# NNLightSwitcher_Zynq.net
KiCad netlist of a schematic drawn in Altium Designer
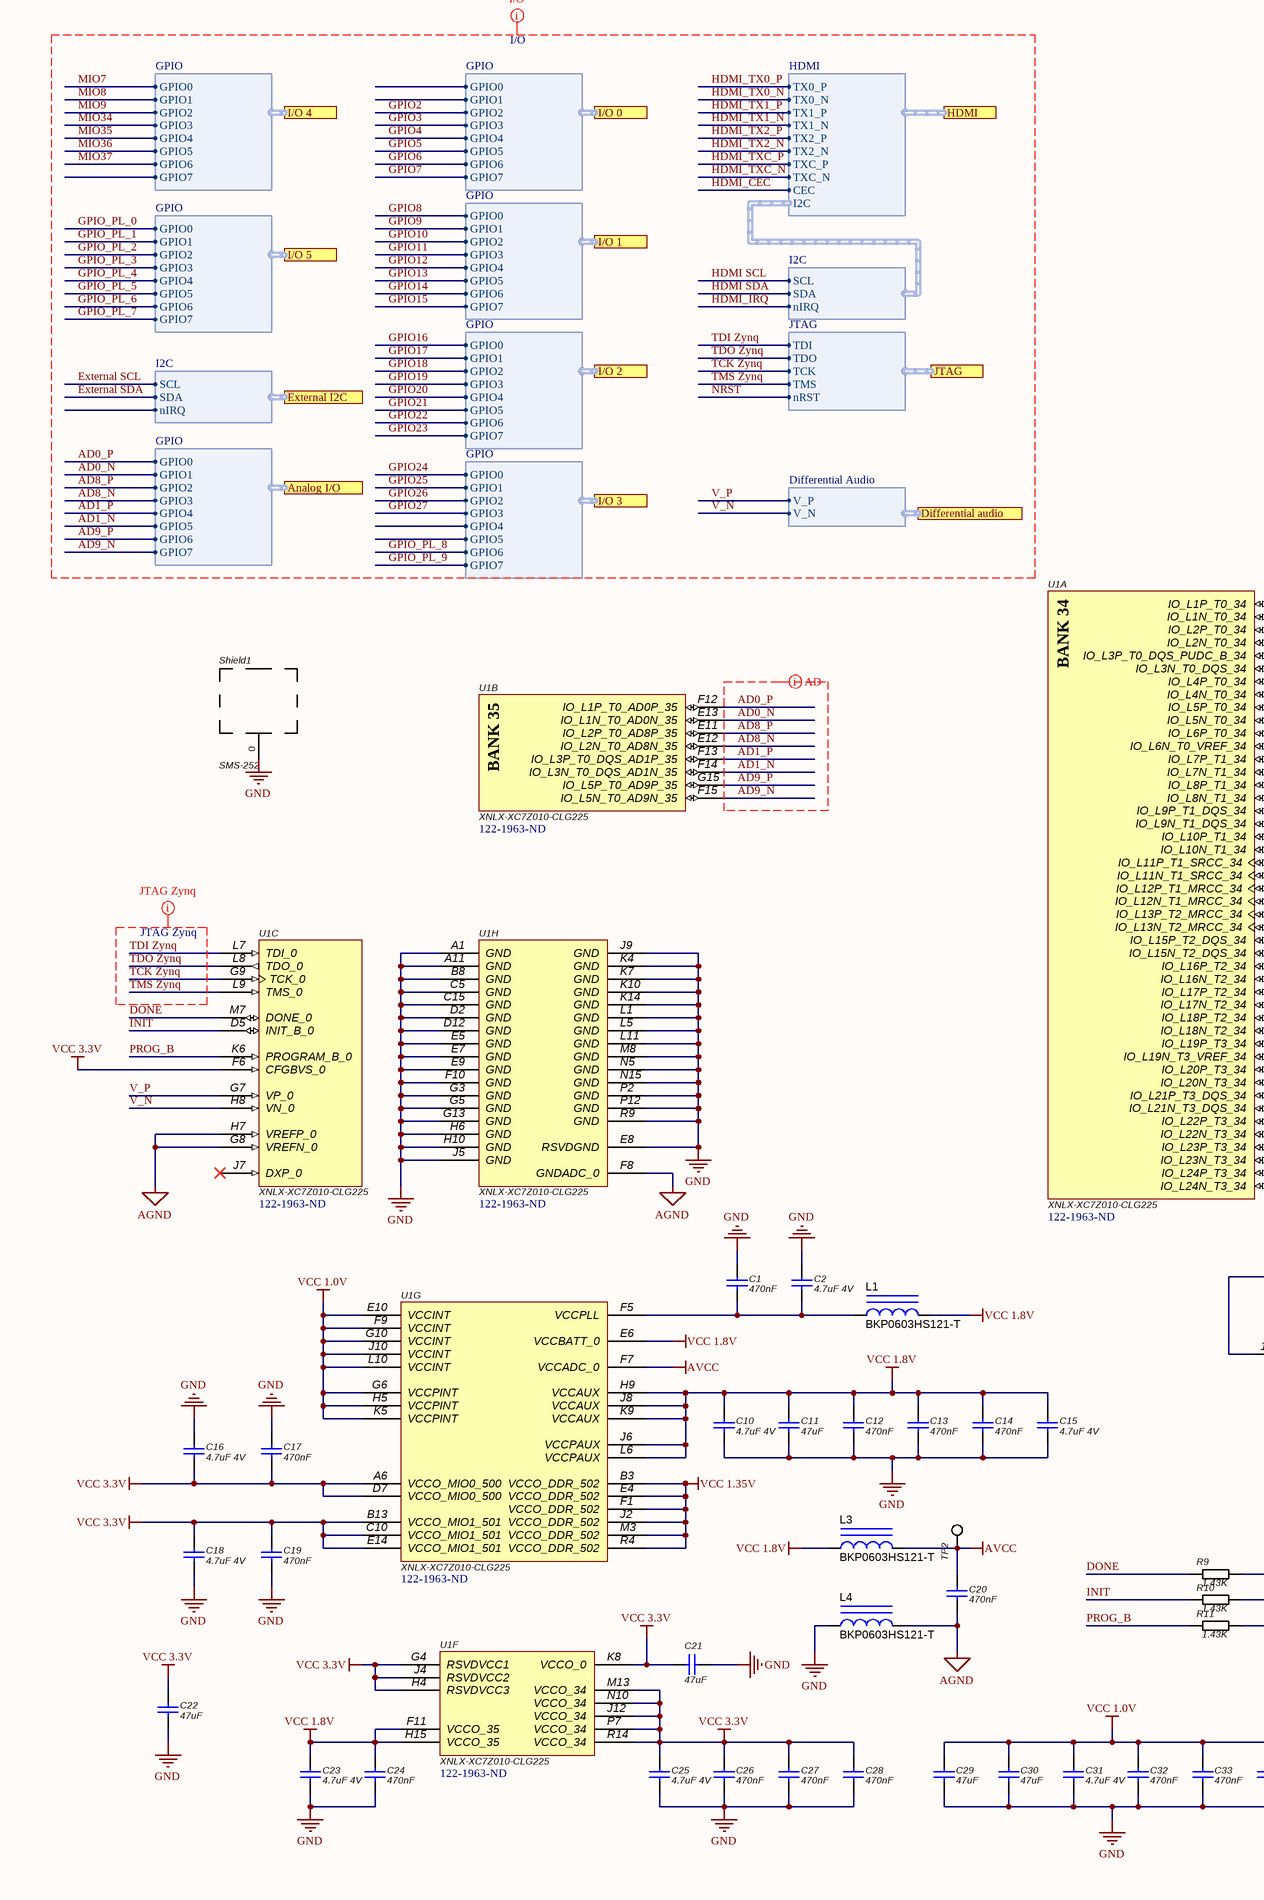
[diagram p0: NNLightSwitcher_Zynq.SchDoc, left]
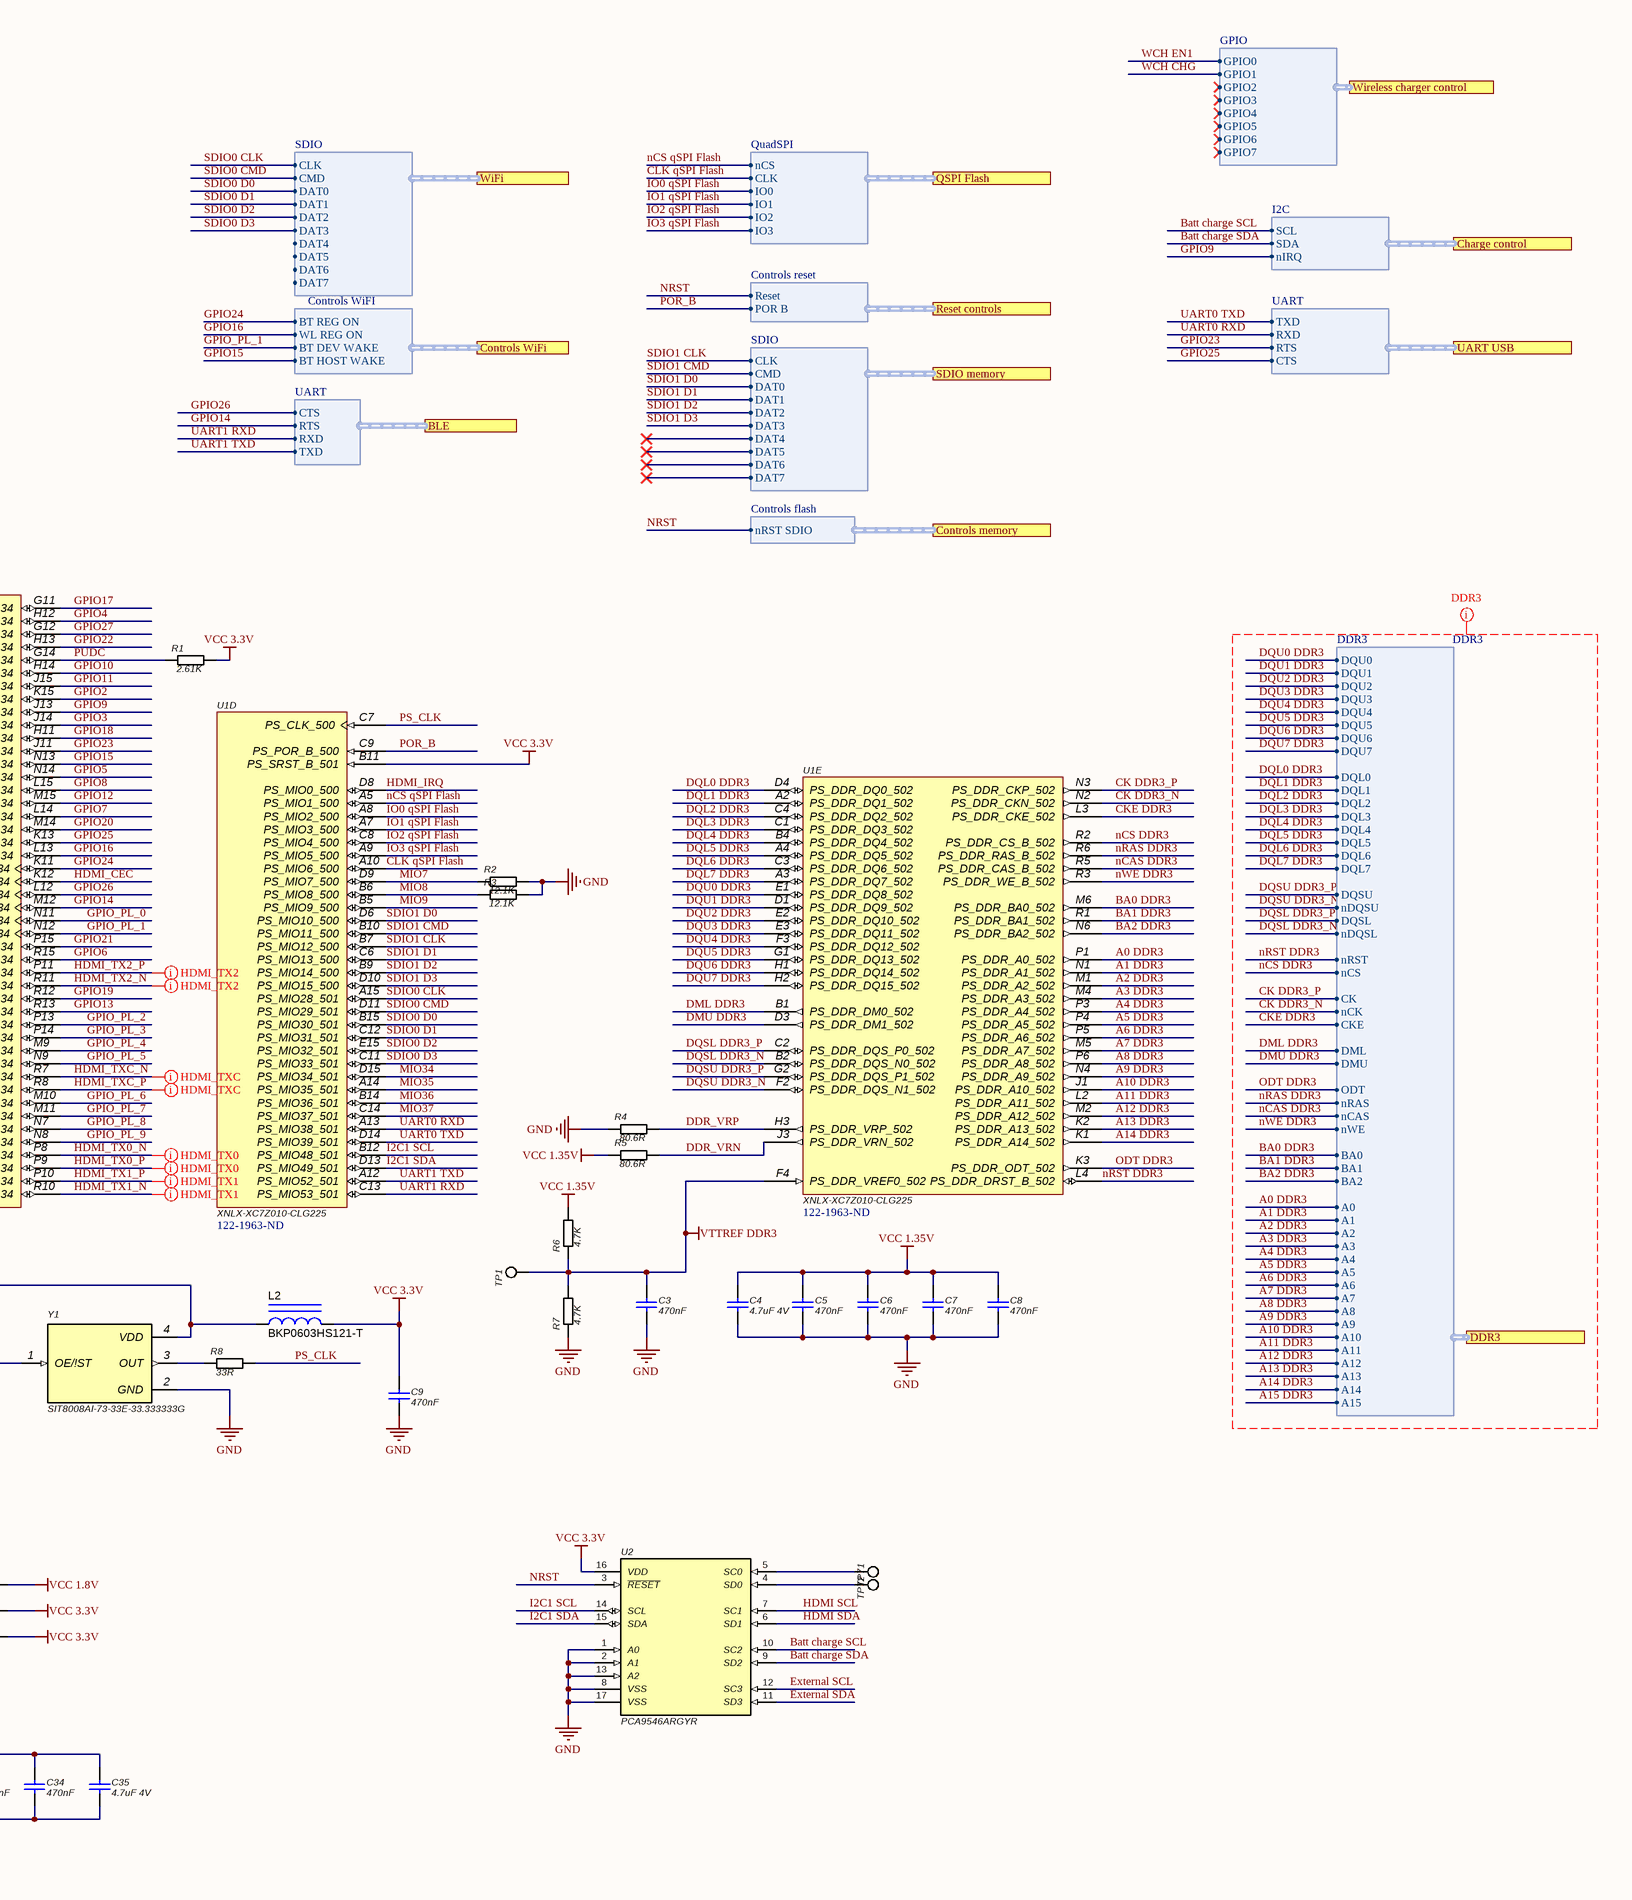
[diagram p1: NNLightSwitcher_Zynq.SchDoc, right]

(export (version "E")
  (design (tool "Eeschema 10.0.6"))
  (components
    (comp (ref "C1")
      (value "470nF")
      (footprint "0402")
      (libsource (lib "NNLightSwitcher") (part "Capacitor 470nF"))
    )
    (comp (ref "C2")
      (value "4.7uF 4V")
      (footprint "0402")
      (libsource (lib "NNLightSwitcher") (part "Capacitor 4.7uF 4V"))
    )
    (comp (ref "C3")
      (value "470nF")
      (footprint "0402")
      (libsource (lib "NNLightSwitcher") (part "Capacitor 470nF"))
    )
    (comp (ref "C4")
      (value "4.7uF 4V")
      (footprint "0402")
      (libsource (lib "NNLightSwitcher") (part "Capacitor 4.7uF 4V"))
    )
    (comp (ref "C5")
      (value "470nF")
      (footprint "0402")
      (libsource (lib "NNLightSwitcher") (part "Capacitor 470nF"))
    )
    (comp (ref "C6")
      (value "470nF")
      (footprint "0402")
      (libsource (lib "NNLightSwitcher") (part "Capacitor 470nF"))
    )
    (comp (ref "C7")
      (value "470nF")
      (footprint "0402")
      (libsource (lib "NNLightSwitcher") (part "Capacitor 470nF"))
    )
    (comp (ref "C8")
      (value "470nF")
      (footprint "0402")
      (libsource (lib "NNLightSwitcher") (part "Capacitor 470nF"))
    )
    (comp (ref "C9")
      (value "470nF")
      (footprint "0402")
      (libsource (lib "NNLightSwitcher") (part "Capacitor 470nF"))
    )
    (comp (ref "C10")
      (value "4.7uF 4V")
      (footprint "0402")
      (libsource (lib "NNLightSwitcher") (part "Capacitor 4.7uF 4V"))
    )
    (comp (ref "C11")
      (value "47uF")
      (footprint "Res_0805")
      (libsource (lib "NNLightSwitcher") (part "Capacitor 47uF"))
    )
    (comp (ref "C12")
      (value "470nF")
      (footprint "0402")
      (libsource (lib "NNLightSwitcher") (part "Capacitor 470nF"))
    )
    (comp (ref "C13")
      (value "470nF")
      (footprint "0402")
      (libsource (lib "NNLightSwitcher") (part "Capacitor 470nF"))
    )
    (comp (ref "C14")
      (value "470nF")
      (footprint "0402")
      (libsource (lib "NNLightSwitcher") (part "Capacitor 470nF"))
    )
    (comp (ref "C15")
      (value "4.7uF 4V")
      (footprint "0402")
      (libsource (lib "NNLightSwitcher") (part "Capacitor 4.7uF 4V"))
    )
    (comp (ref "C16")
      (value "4.7uF 4V")
      (footprint "0402")
      (libsource (lib "NNLightSwitcher") (part "Capacitor 4.7uF 4V"))
    )
    (comp (ref "C17")
      (value "470nF")
      (footprint "0402")
      (libsource (lib "NNLightSwitcher") (part "Capacitor 470nF"))
    )
    (comp (ref "C18")
      (value "4.7uF 4V")
      (footprint "0402")
      (libsource (lib "NNLightSwitcher") (part "Capacitor 4.7uF 4V"))
    )
    (comp (ref "C19")
      (value "470nF")
      (footprint "0402")
      (libsource (lib "NNLightSwitcher") (part "Capacitor 470nF"))
    )
    (comp (ref "C20")
      (value "470nF")
      (footprint "0402")
      (libsource (lib "NNLightSwitcher") (part "Capacitor 470nF"))
    )
    (comp (ref "C21")
      (value "47uF")
      (footprint "Res_0805")
      (libsource (lib "NNLightSwitcher") (part "Capacitor 47uF"))
    )
    (comp (ref "C22")
      (value "47uF")
      (footprint "Res_0805")
      (libsource (lib "NNLightSwitcher") (part "Capacitor 47uF"))
    )
    (comp (ref "C23")
      (value "4.7uF 4V")
      (footprint "0402")
      (libsource (lib "NNLightSwitcher") (part "Capacitor 4.7uF 4V"))
    )
    (comp (ref "C24")
      (value "470nF")
      (footprint "0402")
      (libsource (lib "NNLightSwitcher") (part "Capacitor 470nF"))
    )
    (comp (ref "C25")
      (value "4.7uF 4V")
      (footprint "0402")
      (libsource (lib "NNLightSwitcher") (part "Capacitor 4.7uF 4V"))
    )
    (comp (ref "C26")
      (value "470nF")
      (footprint "0402")
      (libsource (lib "NNLightSwitcher") (part "Capacitor 470nF"))
    )
    (comp (ref "C27")
      (value "470nF")
      (footprint "0402")
      (libsource (lib "NNLightSwitcher") (part "Capacitor 470nF"))
    )
    (comp (ref "C28")
      (value "470nF")
      (footprint "0402")
      (libsource (lib "NNLightSwitcher") (part "Capacitor 470nF"))
    )
    (comp (ref "C29")
      (value "47uF")
      (footprint "Res_0805")
      (libsource (lib "NNLightSwitcher") (part "Capacitor 47uF"))
    )
    (comp (ref "C30")
      (value "47uF")
      (footprint "Res_0805")
      (libsource (lib "NNLightSwitcher") (part "Capacitor 47uF"))
    )
    (comp (ref "C31")
      (value "4.7uF 4V")
      (footprint "0402")
      (libsource (lib "NNLightSwitcher") (part "Capacitor 4.7uF 4V"))
    )
    (comp (ref "C32")
      (value "470nF")
      (footprint "0402")
      (libsource (lib "NNLightSwitcher") (part "Capacitor 470nF"))
    )
    (comp (ref "C33")
      (value "470nF")
      (footprint "0402")
      (libsource (lib "NNLightSwitcher") (part "Capacitor 470nF"))
    )
    (comp (ref "C34")
      (value "470nF")
      (footprint "0402")
      (libsource (lib "NNLightSwitcher") (part "Capacitor 470nF"))
    )
    (comp (ref "C35")
      (value "4.7uF 4V")
      (footprint "0402")
      (libsource (lib "NNLightSwitcher") (part "Capacitor 4.7uF 4V"))
    )
    (comp (ref "L1")
      (value "BKP0603HS121-T")
      (footprint "*0603")
      (description "Inductor, Multilayer, Ferrite bad")
      (fields (field (name "PARTNUMBER") "LQG15HS3N9S02D") (field (name "MANUFACTURER") "MuRata"))
      (libsource (lib "NNLightSwitcher") (part "BKP0603HS121-T"))
    )
    (comp (ref "L2")
      (value "BKP0603HS121-T")
      (footprint "*0603")
      (description "Inductor, Multilayer, Ferrite bad")
      (fields (field (name "PARTNUMBER") "LQG15HS3N9S02D") (field (name "MANUFACTURER") "MuRata"))
      (libsource (lib "NNLightSwitcher") (part "BKP0603HS121-T"))
    )
    (comp (ref "L3")
      (value "BKP0603HS121-T")
      (footprint "*0603")
      (description "Inductor, Multilayer, Ferrite bad")
      (fields (field (name "PARTNUMBER") "LQG15HS3N9S02D") (field (name "MANUFACTURER") "MuRata"))
      (libsource (lib "NNLightSwitcher") (part "BKP0603HS121-T"))
    )
    (comp (ref "L4")
      (value "BKP0603HS121-T")
      (footprint "*0603")
      (description "Inductor, Multilayer, Ferrite bad")
      (fields (field (name "PARTNUMBER") "LQG15HS3N9S02D") (field (name "MANUFACTURER") "MuRata"))
      (libsource (lib "NNLightSwitcher") (part "BKP0603HS121-T"))
    )
    (comp (ref "R1")
      (value "2.61K")
      (footprint "0402")
      (libsource (lib "NNLightSwitcher") (part "Resistor 2.61K"))
    )
    (comp (ref "R2")
      (value "12.1K")
      (footprint "0402")
      (libsource (lib "NNLightSwitcher") (part "Resistor 12.1K"))
    )
    (comp (ref "R3")
      (value "12.1K")
      (footprint "0402")
      (libsource (lib "NNLightSwitcher") (part "Resistor 12.1K"))
    )
    (comp (ref "R4")
      (value "80.6R")
      (footprint "0402")
      (libsource (lib "NNLightSwitcher") (part "Resistor 80.6R"))
    )
    (comp (ref "R5")
      (value "80.6R")
      (footprint "0402")
      (libsource (lib "NNLightSwitcher") (part "Resistor 80.6R"))
    )
    (comp (ref "R6")
      (value "4.7K")
      (footprint "0402")
      (libsource (lib "NNLightSwitcher") (part "Resistor 4.7K"))
    )
    (comp (ref "R7")
      (value "4.7K")
      (footprint "0402")
      (libsource (lib "NNLightSwitcher") (part "Resistor 4.7K"))
    )
    (comp (ref "R8")
      (value "33R")
      (footprint "0402")
      (libsource (lib "NNLightSwitcher") (part "Resistor 33R"))
    )
    (comp (ref "R9")
      (value "1.43K")
      (footprint "0402")
      (libsource (lib "NNLightSwitcher") (part "Resistor 1.43K"))
    )
    (comp (ref "R10")
      (value "1.43K")
      (footprint "0402")
      (libsource (lib "NNLightSwitcher") (part "Resistor 1.43K"))
    )
    (comp (ref "R11")
      (value "1.43K")
      (footprint "0402")
      (libsource (lib "NNLightSwitcher") (part "Resistor 1.43K"))
    )
    (comp (ref "Shield1")
      (value "SMS-252")
      (footprint "shield")
      (description "EMI shield Leader tech SMS-252")
      (libsource (lib "NNLightSwitcher") (part "SMS-252"))
    )
    (comp (ref "TP1")
      (value "Test point")
      (footprint "Testpoint_Keystone_Miniature")
      (description "Test Point, Miniature, SMT")
      (libsource (lib "NNLightSwitcher") (part "Test point"))
    )
    (comp (ref "TP2")
      (value "Test point")
      (footprint "Testpoint_Keystone_Miniature")
      (description "Test Point, Miniature, SMT")
      (libsource (lib "NNLightSwitcher") (part "Test point"))
    )
    (comp (ref "TP71")
      (value "Test point")
      (footprint "Testpoint_Keystone_Miniature")
      (description "Test Point, Miniature, SMT")
      (libsource (lib "NNLightSwitcher") (part "Test point"))
    )
    (comp (ref "TP72")
      (value "Test point")
      (footprint "Testpoint_Keystone_Miniature")
      (description "Test Point, Miniature, SMT")
      (libsource (lib "NNLightSwitcher") (part "Test point"))
    )
    (comp (ref "U1")
      (value "XNLX-XC7Z010-CLG225")
      (footprint "CLG225")
      (description "IC SOC CORTEX-A9 ARTIX-7 225BGA")
      (fields (field (name "SUPPLIER PART NUMBER 1") "122-1963-ND"))
      (libsource (lib "NNLightSwitcher") (part "XNLX-XC7Z010-CLG225"))
    )
    (comp (ref "U2")
      (value "PCA9546ARGYR")
      (footprint "*QFN50P400X350X100-17N(205X255)")
      (description "PCA9546 Series 4-Channel I2C-Bus Switch w/ Interrupt Logic and Rst")
      (libsource (lib "NNLightSwitcher") (part "PCA9546ARGYR"))
    )
    (comp (ref "Y1")
      (value "SIT8008AI-73-33E-33.333333G")
      (footprint "*OSC_SIT8008AI-73-33E-33.333333G")
      (description "Mems Osc, 33.333333MHZ, 2X1.6MM, Lvcmos")
      (libsource (lib "NNLightSwitcher") (part "SIT8008AI-73-33E-33.333333G"))
    )
  )
  (nets
    (net (code "16") (name "/A0 DDR3") (class "Default")
      (node (ref "U1") (pin "P1") (pinfunction "PS_DDR_A0_502_P1") (pintype "output"))
    )
    (net (code "17") (name "/A1 DDR3") (class "Default")
      (node (ref "U1") (pin "N1") (pinfunction "PS_DDR_A1_502_N1") (pintype "output"))
    )
    (net (code "18") (name "/A2 DDR3") (class "Default")
      (node (ref "U1") (pin "M1") (pinfunction "PS_DDR_A2_502_M1") (pintype "output"))
    )
    (net (code "19") (name "/A3 DDR3") (class "Default")
      (node (ref "U1") (pin "M4") (pinfunction "PS_DDR_A3_502_M4") (pintype "output"))
    )
    (net (code "20") (name "/A4 DDR3") (class "Default")
      (node (ref "U1") (pin "P3") (pinfunction "PS_DDR_A4_502_P3") (pintype "output"))
    )
    (net (code "21") (name "/A5 DDR3") (class "Default")
      (node (ref "U1") (pin "P4") (pinfunction "PS_DDR_A5_502_P4") (pintype "output"))
    )
    (net (code "22") (name "/A6 DDR3") (class "Default")
      (node (ref "U1") (pin "P5") (pinfunction "PS_DDR_A6_502_P5") (pintype "output"))
    )
    (net (code "23") (name "/A7 DDR3") (class "Default")
      (node (ref "U1") (pin "M5") (pinfunction "PS_DDR_A7_502_M5") (pintype "output"))
    )
    (net (code "24") (name "/A8 DDR3") (class "Default")
      (node (ref "U1") (pin "P6") (pinfunction "PS_DDR_A8_502_P6") (pintype "output"))
    )
    (net (code "25") (name "/A9 DDR3") (class "Default")
      (node (ref "U1") (pin "N4") (pinfunction "PS_DDR_A9_502_N4") (pintype "output"))
    )
    (net (code "26") (name "/A10 DDR3") (class "Default")
      (node (ref "U1") (pin "J1") (pinfunction "PS_DDR_A10_502_J1") (pintype "output"))
    )
    (net (code "27") (name "/A11 DDR3") (class "Default")
      (node (ref "U1") (pin "L2") (pinfunction "PS_DDR_A11_502_L2") (pintype "output"))
    )
    (net (code "28") (name "/A12 DDR3") (class "Default")
      (node (ref "U1") (pin "M2") (pinfunction "PS_DDR_A12_502_M2") (pintype "output"))
    )
    (net (code "29") (name "/A13 DDR3") (class "Default")
      (node (ref "U1") (pin "K2") (pinfunction "PS_DDR_A13_502_K2") (pintype "output"))
    )
    (net (code "30") (name "/A14 DDR3") (class "Default")
      (node (ref "U1") (pin "K1") (pinfunction "PS_DDR_A14_502_K1") (pintype "output"))
    )
    (net (code "32") (name "/AD0_N") (class "Default")
      (node (ref "U1") (pin "E13") (pinfunction "IO_L1N_T0_AD0N_35_E13") (pintype "bidirectional"))
    )
    (net (code "33") (name "/AD0_P") (class "Default")
      (node (ref "U1") (pin "F12") (pinfunction "IO_L1P_T0_AD0P_35_F12") (pintype "bidirectional"))
    )
    (net (code "34") (name "/AD1_N") (class "Default")
      (node (ref "U1") (pin "F14") (pinfunction "IO_L3N_T0_DQS_AD1N_35_F14") (pintype "bidirectional"))
    )
    (net (code "35") (name "/AD1_P") (class "Default")
      (node (ref "U1") (pin "F13") (pinfunction "IO_L3P_T0_DQS_AD1P_35_F13") (pintype "bidirectional"))
    )
    (net (code "36") (name "/AD8_N") (class "Default")
      (node (ref "U1") (pin "E12") (pinfunction "IO_L2N_T0_AD8N_35_E12") (pintype "bidirectional"))
    )
    (net (code "37") (name "/AD8_P") (class "Default")
      (node (ref "U1") (pin "E11") (pinfunction "IO_L2P_T0_AD8P_35_E11") (pintype "bidirectional"))
    )
    (net (code "38") (name "/AD9_N") (class "Default")
      (node (ref "U1") (pin "F15") (pinfunction "IO_L5N_T0_AD9N_35_F15") (pintype "bidirectional"))
    )
    (net (code "39") (name "/AD9_P") (class "Default")
      (node (ref "U1") (pin "G15") (pinfunction "IO_L5P_T0_AD9P_35_G15") (pintype "bidirectional"))
    )
    (net (code "40") (name "/BA0 DDR3") (class "Default")
      (node (ref "U1") (pin "M6") (pinfunction "PS_DDR_BA0_502_M6") (pintype "output"))
    )
    (net (code "41") (name "/BA1 DDR3") (class "Default")
      (node (ref "U1") (pin "R1") (pinfunction "PS_DDR_BA1_502_R1") (pintype "output"))
    )
    (net (code "42") (name "/BA2 DDR3") (class "Default")
      (node (ref "U1") (pin "N6") (pinfunction "PS_DDR_BA2_502_N6") (pintype "output"))
    )
    (net (code "43") (name "/Batt charge SCL") (class "Default")
      (node (ref "U2") (pin "10") (pinfunction "SC2_10") (pintype "input"))
    )
    (net (code "44") (name "/Batt charge SDA") (class "Default")
      (node (ref "U2") (pin "9") (pinfunction "SD2_9") (pintype "input"))
    )
    (net (code "45") (name "/CK DDR3_N") (class "Default")
      (node (ref "U1") (pin "N2") (pinfunction "PS_DDR_CKN_502_N2") (pintype "output"))
    )
    (net (code "46") (name "/CK DDR3_P") (class "Default")
      (node (ref "U1") (pin "N3") (pinfunction "PS_DDR_CKP_502_N3") (pintype "output"))
    )
    (net (code "47") (name "/CKE DDR3") (class "Default")
      (node (ref "U1") (pin "L3") (pinfunction "PS_DDR_CKE_502_L3") (pintype "output"))
    )
    (net (code "48") (name "/CLK qSPI Flash") (class "Default")
      (node (ref "U1") (pin "A10") (pinfunction "PS_MIO6_500_A10") (pintype "bidirectional"))
    )
    (net (code "49") (name "/DDR_VRN") (class "Default")
      (node (ref "R5") (pin "2") (pinfunction "2_2") (pintype "passive"))
      (node (ref "U1") (pin "J3") (pinfunction "PS_DDR_VRN_502_J3") (pintype "output"))
    )
    (net (code "50") (name "/DDR_VRP") (class "Default")
      (node (ref "R4") (pin "2") (pinfunction "2_2") (pintype "passive"))
      (node (ref "U1") (pin "H3") (pinfunction "PS_DDR_VRP_502_H3") (pintype "output"))
    )
    (net (code "51") (name "/DML DDR3") (class "Default")
      (node (ref "U1") (pin "B1") (pinfunction "PS_DDR_DM0_502_B1") (pintype "output"))
    )
    (net (code "52") (name "/DMU DDR3") (class "Default")
      (node (ref "U1") (pin "D3") (pinfunction "PS_DDR_DM1_502_D3") (pintype "output"))
    )
    (net (code "53") (name "/DONE") (class "Default")
      (node (ref "R9") (pin "1") (pinfunction "1_1") (pintype "passive"))
      (node (ref "U1") (pin "M7") (pinfunction "DONE_0_M7") (pintype "bidirectional"))
    )
    (net (code "54") (name "/DQL0 DDR3") (class "Default")
      (node (ref "U1") (pin "D4") (pinfunction "PS_DDR_DQ0_502_D4") (pintype "bidirectional"))
    )
    (net (code "55") (name "/DQL1 DDR3") (class "Default")
      (node (ref "U1") (pin "A2") (pinfunction "PS_DDR_DQ1_502_A2") (pintype "bidirectional"))
    )
    (net (code "56") (name "/DQL2 DDR3") (class "Default")
      (node (ref "U1") (pin "C4") (pinfunction "PS_DDR_DQ2_502_C4") (pintype "bidirectional"))
    )
    (net (code "57") (name "/DQL3 DDR3") (class "Default")
      (node (ref "U1") (pin "C1") (pinfunction "PS_DDR_DQ3_502_C1") (pintype "bidirectional"))
    )
    (net (code "58") (name "/DQL4 DDR3") (class "Default")
      (node (ref "U1") (pin "B4") (pinfunction "PS_DDR_DQ4_502_B4") (pintype "bidirectional"))
    )
    (net (code "59") (name "/DQL5 DDR3") (class "Default")
      (node (ref "U1") (pin "A4") (pinfunction "PS_DDR_DQ5_502_A4") (pintype "bidirectional"))
    )
    (net (code "60") (name "/DQL6 DDR3") (class "Default")
      (node (ref "U1") (pin "C3") (pinfunction "PS_DDR_DQ6_502_C3") (pintype "bidirectional"))
    )
    (net (code "61") (name "/DQL7 DDR3") (class "Default")
      (node (ref "U1") (pin "A3") (pinfunction "PS_DDR_DQ7_502_A3") (pintype "bidirectional"))
    )
    (net (code "62") (name "/DQSL DDR3_N") (class "Default")
      (node (ref "U1") (pin "B2") (pinfunction "PS_DDR_DQS_N0_502_B2") (pintype "bidirectional"))
    )
    (net (code "63") (name "/DQSL DDR3_P") (class "Default")
      (node (ref "U1") (pin "C2") (pinfunction "PS_DDR_DQS_P0_502_C2") (pintype "bidirectional"))
    )
    (net (code "64") (name "/DQSU DDR3_N") (class "Default")
      (node (ref "U1") (pin "F2") (pinfunction "PS_DDR_DQS_N1_502_F2") (pintype "bidirectional"))
    )
    (net (code "65") (name "/DQSU DDR3_P") (class "Default")
      (node (ref "U1") (pin "G2") (pinfunction "PS_DDR_DQS_P1_502_G2") (pintype "bidirectional"))
    )
    (net (code "66") (name "/DQU0 DDR3") (class "Default")
      (node (ref "U1") (pin "E1") (pinfunction "PS_DDR_DQ8_502_E1") (pintype "bidirectional"))
    )
    (net (code "67") (name "/DQU1 DDR3") (class "Default")
      (node (ref "U1") (pin "D1") (pinfunction "PS_DDR_DQ9_502_D1") (pintype "bidirectional"))
    )
    (net (code "68") (name "/DQU2 DDR3") (class "Default")
      (node (ref "U1") (pin "E2") (pinfunction "PS_DDR_DQ10_502_E2") (pintype "bidirectional"))
    )
    (net (code "69") (name "/DQU3 DDR3") (class "Default")
      (node (ref "U1") (pin "E3") (pinfunction "PS_DDR_DQ11_502_E3") (pintype "bidirectional"))
    )
    (net (code "70") (name "/DQU4 DDR3") (class "Default")
      (node (ref "U1") (pin "F3") (pinfunction "PS_DDR_DQ12_502_F3") (pintype "bidirectional"))
    )
    (net (code "71") (name "/DQU5 DDR3") (class "Default")
      (node (ref "U1") (pin "G1") (pinfunction "PS_DDR_DQ13_502_G1") (pintype "bidirectional"))
    )
    (net (code "72") (name "/DQU6 DDR3") (class "Default")
      (node (ref "U1") (pin "H1") (pinfunction "PS_DDR_DQ14_502_H1") (pintype "bidirectional"))
    )
    (net (code "73") (name "/DQU7 DDR3") (class "Default")
      (node (ref "U1") (pin "H2") (pinfunction "PS_DDR_DQ15_502_H2") (pintype "bidirectional"))
    )
    (net (code "74") (name "/External SCL") (class "Default")
      (node (ref "U2") (pin "12") (pinfunction "SC3_12") (pintype "input"))
    )
    (net (code "75") (name "/External SDA") (class "Default")
      (node (ref "U2") (pin "11") (pinfunction "SD3_11") (pintype "input"))
    )
    (net (code "76") (name "/GPIO2") (class "Default")
      (node (ref "U1") (pin "K15") (pinfunction "IO_L4N_T0_34_K15") (pintype "bidirectional"))
    )
    (net (code "77") (name "/GPIO3") (class "Default")
      (node (ref "U1") (pin "J14") (pinfunction "IO_L5N_T0_34_J14") (pintype "bidirectional"))
    )
    (net (code "78") (name "/GPIO4") (class "Default")
      (node (ref "U1") (pin "H12") (pinfunction "IO_L1N_T0_34_H12") (pintype "bidirectional"))
    )
    (net (code "79") (name "/GPIO5") (class "Default")
      (node (ref "U1") (pin "N14") (pinfunction "IO_L7N_T1_34_N14") (pintype "bidirectional"))
    )
    (net (code "80") (name "/GPIO6") (class "Default")
      (node (ref "U1") (pin "R15") (pinfunction "IO_L15N_T2_DQS_34_R15") (pintype "bidirectional"))
    )
    (net (code "81") (name "/GPIO7") (class "Default")
      (node (ref "U1") (pin "L14") (pinfunction "IO_L9P_T1_DQS_34_L14") (pintype "bidirectional"))
    )
    (net (code "82") (name "/GPIO8") (class "Default")
      (node (ref "U1") (pin "L15") (pinfunction "IO_L8P_T1_34_L15") (pintype "bidirectional"))
    )
    (net (code "83") (name "/GPIO9") (class "Default")
      (node (ref "U1") (pin "J13") (pinfunction "IO_L5P_T0_34_J13") (pintype "bidirectional"))
    )
    (net (code "84") (name "/GPIO10") (class "Default")
      (node (ref "U1") (pin "H14") (pinfunction "IO_L3N_T0_DQS_34_H14") (pintype "bidirectional"))
    )
    (net (code "85") (name "/GPIO11") (class "Default")
      (node (ref "U1") (pin "J15") (pinfunction "IO_L4P_T0_34_J15") (pintype "bidirectional"))
    )
    (net (code "86") (name "/GPIO12") (class "Default")
      (node (ref "U1") (pin "M15") (pinfunction "IO_L8N_T1_34_M15") (pintype "bidirectional"))
    )
    (net (code "87") (name "/GPIO13") (class "Default")
      (node (ref "U1") (pin "R13") (pinfunction "IO_L17N_T2_34_R13") (pintype "bidirectional"))
    )
    (net (code "88") (name "/GPIO14") (class "Default")
      (node (ref "U1") (pin "M12") (pinfunction "IO_L12N_T1_MRCC_34_M12") (pintype "bidirectional"))
    )
    (net (code "89") (name "/GPIO15") (class "Default")
      (node (ref "U1") (pin "N13") (pinfunction "IO_L7P_T1_34_N13") (pintype "bidirectional"))
    )
    (net (code "90") (name "/GPIO16") (class "Default")
      (node (ref "U1") (pin "L13") (pinfunction "IO_L10N_T1_34_L13") (pintype "bidirectional"))
    )
    (net (code "91") (name "/GPIO17") (class "Default")
      (node (ref "U1") (pin "G11") (pinfunction "IO_L1P_T0_34_G11") (pintype "bidirectional"))
    )
    (net (code "92") (name "/GPIO18") (class "Default")
      (node (ref "U1") (pin "H11") (pinfunction "IO_L6P_T0_34_H11") (pintype "bidirectional"))
    )
    (net (code "93") (name "/GPIO19") (class "Default")
      (node (ref "U1") (pin "R12") (pinfunction "IO_L17P_T2_34_R12") (pintype "bidirectional"))
    )
    (net (code "94") (name "/GPIO20") (class "Default")
      (node (ref "U1") (pin "M14") (pinfunction "IO_L9N_T1_DQS_34_M14") (pintype "bidirectional"))
    )
    (net (code "95") (name "/GPIO21") (class "Default")
      (node (ref "U1") (pin "P15") (pinfunction "IO_L15P_T2_DQS_34_P15") (pintype "bidirectional"))
    )
    (net (code "96") (name "/GPIO22") (class "Default")
      (node (ref "U1") (pin "H13") (pinfunction "IO_L2N_T0_34_H13") (pintype "bidirectional"))
    )
    (net (code "97") (name "/GPIO23") (class "Default")
      (node (ref "U1") (pin "J11") (pinfunction "IO_L6N_T0_VREF_34_J11") (pintype "bidirectional"))
    )
    (net (code "98") (name "/GPIO24") (class "Default")
      (node (ref "U1") (pin "K11") (pinfunction "IO_L11P_T1_SRCC_34_K11") (pintype "bidirectional"))
    )
    (net (code "99") (name "/GPIO25") (class "Default")
      (node (ref "U1") (pin "K13") (pinfunction "IO_L10P_T1_34_K13") (pintype "bidirectional"))
    )
    (net (code "100") (name "/GPIO26") (class "Default")
      (node (ref "U1") (pin "L12") (pinfunction "IO_L12P_T1_MRCC_34_L12") (pintype "bidirectional"))
    )
    (net (code "101") (name "/GPIO27") (class "Default")
      (node (ref "U1") (pin "G12") (pinfunction "IO_L2P_T0_34_G12") (pintype "bidirectional"))
    )
    (net (code "102") (name "/GPIO_PL_0") (class "Default")
      (node (ref "U1") (pin "N11") (pinfunction "IO_L13P_T2_MRCC_34_N11") (pintype "bidirectional"))
    )
    (net (code "103") (name "/GPIO_PL_1") (class "Default")
      (node (ref "U1") (pin "N12") (pinfunction "IO_L13N_T2_MRCC_34_N12") (pintype "bidirectional"))
    )
    (net (code "104") (name "/GPIO_PL_2") (class "Default")
      (node (ref "U1") (pin "P13") (pinfunction "IO_L18P_T2_34_P13") (pintype "bidirectional"))
    )
    (net (code "105") (name "/GPIO_PL_3") (class "Default")
      (node (ref "U1") (pin "P14") (pinfunction "IO_L18N_T2_34_P14") (pintype "bidirectional"))
    )
    (net (code "106") (name "/GPIO_PL_4") (class "Default")
      (node (ref "U1") (pin "M9") (pinfunction "IO_L19P_T3_34_M9") (pintype "bidirectional"))
    )
    (net (code "107") (name "/GPIO_PL_5") (class "Default")
      (node (ref "U1") (pin "N9") (pinfunction "IO_L19N_T3_VREF_34_N9") (pintype "bidirectional"))
    )
    (net (code "108") (name "/GPIO_PL_6") (class "Default")
      (node (ref "U1") (pin "M10") (pinfunction "IO_L21P_T3_DQS_34_M10") (pintype "bidirectional"))
    )
    (net (code "109") (name "/GPIO_PL_7") (class "Default")
      (node (ref "U1") (pin "M11") (pinfunction "IO_L21N_T3_DQS_34_M11") (pintype "bidirectional"))
    )
    (net (code "110") (name "/GPIO_PL_8") (class "Default")
      (node (ref "U1") (pin "N7") (pinfunction "IO_L22P_T3_34_N7") (pintype "bidirectional"))
    )
    (net (code "111") (name "/GPIO_PL_9") (class "Default")
      (node (ref "U1") (pin "N8") (pinfunction "IO_L22N_T3_34_N8") (pintype "bidirectional"))
    )
    (net (code "112") (name "/HDMI SCL") (class "Default")
      (node (ref "U2") (pin "7") (pinfunction "SC1_7") (pintype "input"))
    )
    (net (code "113") (name "/HDMI SDA") (class "Default")
      (node (ref "U2") (pin "6") (pinfunction "SD1_6") (pintype "input"))
    )
    (net (code "114") (name "/HDMI_CEC") (class "Default")
      (node (ref "U1") (pin "K12") (pinfunction "IO_L11N_T1_SRCC_34_K12") (pintype "bidirectional"))
    )
    (net (code "115") (name "/HDMI_IRQ") (class "Default")
      (node (ref "U1") (pin "D8") (pinfunction "PS_MIO0_500_D8") (pintype "bidirectional"))
    )
    (net (code "116") (name "/HDMI_TX0_N") (class "Default")
      (node (ref "U1") (pin "P8") (pinfunction "IO_L23P_T3_34_P8") (pintype "bidirectional"))
    )
    (net (code "117") (name "/HDMI_TX0_P") (class "Default")
      (node (ref "U1") (pin "P9") (pinfunction "IO_L23N_T3_34_P9") (pintype "bidirectional"))
    )
    (net (code "118") (name "/HDMI_TX1_N") (class "Default")
      (node (ref "U1") (pin "R10") (pinfunction "IO_L24N_T3_34_R10") (pintype "bidirectional"))
    )
    (net (code "119") (name "/HDMI_TX1_P") (class "Default")
      (node (ref "U1") (pin "P10") (pinfunction "IO_L24P_T3_34_P10") (pintype "bidirectional"))
    )
    (net (code "120") (name "/HDMI_TX2_N") (class "Default")
      (node (ref "U1") (pin "R11") (pinfunction "IO_L16N_T2_34_R11") (pintype "bidirectional"))
    )
    (net (code "121") (name "/HDMI_TX2_P") (class "Default")
      (node (ref "U1") (pin "P11") (pinfunction "IO_L16P_T2_34_P11") (pintype "bidirectional"))
    )
    (net (code "122") (name "/HDMI_TXC_N") (class "Default")
      (node (ref "U1") (pin "R7") (pinfunction "IO_L20P_T3_34_R7") (pintype "bidirectional"))
    )
    (net (code "123") (name "/HDMI_TXC_P") (class "Default")
      (node (ref "U1") (pin "R8") (pinfunction "IO_L20N_T3_34_R8") (pintype "bidirectional"))
    )
    (net (code "125") (name "/I2C1 SCL") (class "Default")
      (node (ref "U1") (pin "B12") (pinfunction "PS_MIO48_501_B12") (pintype "bidirectional"))
      (node (ref "U2") (pin "14") (pinfunction "SCL_14") (pintype "bidirectional"))
    )
    (net (code "126") (name "/I2C1 SDA") (class "Default")
      (node (ref "U1") (pin "D13") (pinfunction "PS_MIO49_501_D13") (pintype "bidirectional"))
      (node (ref "U2") (pin "15") (pinfunction "SDA_15") (pintype "bidirectional"))
    )
    (net (code "127") (name "/INIT") (class "Default")
      (node (ref "R10") (pin "1") (pinfunction "1_1") (pintype "passive"))
      (node (ref "U1") (pin "D5") (pinfunction "INIT_B_0_D5") (pintype "bidirectional"))
    )
    (net (code "128") (name "/IO0 qSPI Flash") (class "Default")
      (node (ref "U1") (pin "A8") (pinfunction "PS_MIO2_500_A8") (pintype "bidirectional"))
    )
    (net (code "129") (name "/IO1 qSPI Flash") (class "Default")
      (node (ref "U1") (pin "A7") (pinfunction "PS_MIO3_500_A7") (pintype "bidirectional"))
    )
    (net (code "130") (name "/IO2 qSPI Flash") (class "Default")
      (node (ref "U1") (pin "C8") (pinfunction "PS_MIO4_500_C8") (pintype "bidirectional"))
    )
    (net (code "131") (name "/IO3 qSPI Flash") (class "Default")
      (node (ref "U1") (pin "A9") (pinfunction "PS_MIO5_500_A9") (pintype "bidirectional"))
    )
    (net (code "132") (name "/MIO7") (class "Default")
      (node (ref "R2") (pin "1") (pinfunction "1_1") (pintype "passive"))
      (node (ref "U1") (pin "D9") (pinfunction "PS_MIO7_500_D9") (pintype "bidirectional"))
    )
    (net (code "133") (name "/MIO8") (class "Default")
      (node (ref "R3") (pin "1") (pinfunction "1_1") (pintype "passive"))
      (node (ref "U1") (pin "B6") (pinfunction "PS_MIO8_500_B6") (pintype "bidirectional"))
    )
    (net (code "134") (name "/MIO9") (class "Default")
      (node (ref "U1") (pin "B5") (pinfunction "PS_MIO9_500_B5") (pintype "bidirectional"))
    )
    (net (code "135") (name "/MIO34") (class "Default")
      (node (ref "U1") (pin "D15") (pinfunction "PS_MIO34_501_D15") (pintype "bidirectional"))
    )
    (net (code "136") (name "/MIO35") (class "Default")
      (node (ref "U1") (pin "A14") (pinfunction "PS_MIO35_501_A14") (pintype "bidirectional"))
    )
    (net (code "137") (name "/MIO36") (class "Default")
      (node (ref "U1") (pin "B14") (pinfunction "PS_MIO36_501_B14") (pintype "bidirectional"))
    )
    (net (code "138") (name "/MIO37") (class "Default")
      (node (ref "U1") (pin "C14") (pinfunction "PS_MIO37_501_C14") (pintype "bidirectional"))
    )
    (net (code "139") (name "/NRST") (class "Default")
      (node (ref "U2") (pin "3") (pinfunction "~{RESET}_3") (pintype "input"))
    )
    (net (code "140") (name "/ODT DDR3") (class "Default")
      (node (ref "U1") (pin "K3") (pinfunction "PS_DDR_ODT_502_K3") (pintype "output"))
    )
    (net (code "141") (name "/POR_B") (class "Default")
      (node (ref "U1") (pin "C9") (pinfunction "PS_POR_B_500_C9") (pintype "input"))
    )
    (net (code "142") (name "/PROG_B") (class "Default")
      (node (ref "R11") (pin "1") (pinfunction "1_1") (pintype "passive"))
      (node (ref "U1") (pin "K6") (pinfunction "PROGRAM_B_0_K6") (pintype "input"))
    )
    (net (code "143") (name "/PS_CLK") (class "Default")
      (node (ref "R8") (pin "2") (pinfunction "2_2") (pintype "passive"))
      (node (ref "U1") (pin "C7") (pinfunction "PS_CLK_500_C7") (pintype "input"))
    )
    (net (code "144") (name "/PUDC") (class "Default")
      (node (ref "R1") (pin "1") (pinfunction "1_1") (pintype "passive"))
      (node (ref "U1") (pin "G14") (pinfunction "IO_L3P_T0_DQS_PUDC_B_34_G14") (pintype "bidirectional"))
    )
    (net (code "145") (name "/SDIO0 CLK") (class "Default")
      (node (ref "U1") (pin "A15") (pinfunction "PS_MIO28_501_A15") (pintype "bidirectional"))
    )
    (net (code "146") (name "/SDIO0 CMD") (class "Default")
      (node (ref "U1") (pin "D11") (pinfunction "PS_MIO29_501_D11") (pintype "bidirectional"))
    )
    (net (code "147") (name "/SDIO0 D0") (class "Default")
      (node (ref "U1") (pin "B15") (pinfunction "PS_MIO30_501_B15") (pintype "bidirectional"))
    )
    (net (code "148") (name "/SDIO0 D1") (class "Default")
      (node (ref "U1") (pin "C12") (pinfunction "PS_MIO31_501_C12") (pintype "bidirectional"))
    )
    (net (code "149") (name "/SDIO0 D2") (class "Default")
      (node (ref "U1") (pin "E15") (pinfunction "PS_MIO32_501_E15") (pintype "bidirectional"))
    )
    (net (code "150") (name "/SDIO0 D3") (class "Default")
      (node (ref "U1") (pin "C11") (pinfunction "PS_MIO33_501_C11") (pintype "bidirectional"))
    )
    (net (code "151") (name "/SDIO1 CLK") (class "Default")
      (node (ref "U1") (pin "B7") (pinfunction "PS_MIO12_500_B7") (pintype "bidirectional"))
    )
    (net (code "152") (name "/SDIO1 CMD") (class "Default")
      (node (ref "U1") (pin "B10") (pinfunction "PS_MIO11_500_B10") (pintype "bidirectional"))
    )
    (net (code "153") (name "/SDIO1 D0") (class "Default")
      (node (ref "U1") (pin "D6") (pinfunction "PS_MIO10_500_D6") (pintype "bidirectional"))
    )
    (net (code "154") (name "/SDIO1 D1") (class "Default")
      (node (ref "U1") (pin "C6") (pinfunction "PS_MIO13_500_C6") (pintype "bidirectional"))
    )
    (net (code "155") (name "/SDIO1 D2") (class "Default")
      (node (ref "U1") (pin "B9") (pinfunction "PS_MIO14_500_B9") (pintype "bidirectional"))
    )
    (net (code "156") (name "/SDIO1 D3") (class "Default")
      (node (ref "U1") (pin "D10") (pinfunction "PS_MIO15_500_D10") (pintype "bidirectional"))
    )
    (net (code "157") (name "/TCK Zynq") (class "Default")
      (node (ref "U1") (pin "G9") (pinfunction "TCK_0_G9") (pintype "input"))
    )
    (net (code "158") (name "/TDI Zynq") (class "Default")
      (node (ref "U1") (pin "L7") (pinfunction "TDI_0_L7") (pintype "input"))
    )
    (net (code "159") (name "/TDO Zynq") (class "Default")
      (node (ref "U1") (pin "L8") (pinfunction "TDO_0_L8") (pintype "output"))
    )
    (net (code "160") (name "/TMS Zynq") (class "Default")
      (node (ref "U1") (pin "L9") (pinfunction "TMS_0_L9") (pintype "input"))
    )
    (net (code "161") (name "/UART0 RXD") (class "Default")
      (node (ref "U1") (pin "A13") (pinfunction "PS_MIO38_501_A13") (pintype "bidirectional"))
    )
    (net (code "162") (name "/UART0 TXD") (class "Default")
      (node (ref "U1") (pin "D14") (pinfunction "PS_MIO39_501_D14") (pintype "bidirectional"))
    )
    (net (code "163") (name "/UART1 RXD") (class "Default")
      (node (ref "U1") (pin "C13") (pinfunction "PS_MIO53_501_C13") (pintype "bidirectional"))
    )
    (net (code "164") (name "/UART1 TXD") (class "Default")
      (node (ref "U1") (pin "A12") (pinfunction "PS_MIO52_501_A12") (pintype "bidirectional"))
    )
    (net (code "165") (name "/V_N") (class "Default")
      (node (ref "U1") (pin "H8") (pinfunction "VN_0_H8") (pintype "input"))
    )
    (net (code "166") (name "/V_P") (class "Default")
      (node (ref "U1") (pin "G7") (pinfunction "VP_0_G7") (pintype "input"))
    )
    (net (code "169") (name "/nCAS DDR3") (class "Default")
      (node (ref "U1") (pin "R5") (pinfunction "PS_DDR_CAS_B_502_R5") (pintype "output"))
    )
    (net (code "170") (name "/nCS DDR3") (class "Default")
      (node (ref "U1") (pin "R2") (pinfunction "PS_DDR_CS_B_502_R2") (pintype "output"))
    )
    (net (code "171") (name "/nCS qSPI Flash") (class "Default")
      (node (ref "U1") (pin "A5") (pinfunction "PS_MIO1_500_A5") (pintype "bidirectional"))
    )
    (net (code "172") (name "/nRAS DDR3") (class "Default")
      (node (ref "U1") (pin "R6") (pinfunction "PS_DDR_RAS_B_502_R6") (pintype "output"))
    )
    (net (code "173") (name "/nRST DDR3") (class "Default")
      (node (ref "U1") (pin "L4") (pinfunction "PS_DDR_DRST_B_502_L4") (pintype "bidirectional"))
    )
    (net (code "174") (name "/nWE DDR3") (class "Default")
      (node (ref "U1") (pin "R3") (pinfunction "PS_DDR_WE_B_502_R3") (pintype "output"))
    )
    (net (code "187") (name "AGND") (class "Default")
      (node (ref "C20") (pin "2") (pinfunction "2_2") (pintype "passive"))
      (node (ref "L4") (pin "2") (pinfunction "2_2") (pintype "passive"))
      (node (ref "U1") (pin "F8") (pinfunction "GNDADC_0_F8") (pintype "power_in"))
      (node (ref "U1") (pin "G8") (pinfunction "VREFN_0_G8") (pintype "input"))
      (node (ref "U1") (pin "H7") (pinfunction "VREFP_0_H7") (pintype "input"))
    )
    (net (code "188") (name "AVCC") (class "Default")
      (node (ref "C20") (pin "1") (pinfunction "1_1") (pintype "passive"))
      (node (ref "L3") (pin "2") (pinfunction "2_2") (pintype "passive"))
      (node (ref "TP2") (pin "1") (pintype "passive"))
      (node (ref "U1") (pin "F7") (pinfunction "VCCADC_0_F7") (pintype "power_in"))
    )
    (net (code "189") (name "GND") (class "Default")
      (node (ref "C1") (pin "1") (pinfunction "1_1") (pintype "passive"))
      (node (ref "C10") (pin "2") (pinfunction "2_2") (pintype "passive"))
      (node (ref "C11") (pin "2") (pinfunction "2_2") (pintype "passive"))
      (node (ref "C12") (pin "2") (pinfunction "2_2") (pintype "passive"))
      (node (ref "C13") (pin "2") (pinfunction "2_2") (pintype "passive"))
      (node (ref "C14") (pin "2") (pinfunction "2_2") (pintype "passive"))
      (node (ref "C15") (pin "2") (pinfunction "2_2") (pintype "passive"))
      (node (ref "C16") (pin "1") (pinfunction "1_1") (pintype "passive"))
      (node (ref "C17") (pin "1") (pinfunction "1_1") (pintype "passive"))
      (node (ref "C18") (pin "2") (pinfunction "2_2") (pintype "passive"))
      (node (ref "C19") (pin "2") (pinfunction "2_2") (pintype "passive"))
      (node (ref "C2") (pin "1") (pinfunction "1_1") (pintype "passive"))
      (node (ref "C21") (pin "1") (pinfunction "1_1") (pintype "passive"))
      (node (ref "C22") (pin "2") (pinfunction "2_2") (pintype "passive"))
      (node (ref "C23") (pin "2") (pinfunction "2_2") (pintype "passive"))
      (node (ref "C24") (pin "2") (pinfunction "2_2") (pintype "passive"))
      (node (ref "C25") (pin "2") (pinfunction "2_2") (pintype "passive"))
      (node (ref "C26") (pin "2") (pinfunction "2_2") (pintype "passive"))
      (node (ref "C27") (pin "2") (pinfunction "2_2") (pintype "passive"))
      (node (ref "C28") (pin "2") (pinfunction "2_2") (pintype "passive"))
      (node (ref "C29") (pin "2") (pinfunction "2_2") (pintype "passive"))
      (node (ref "C3") (pin "2") (pinfunction "2_2") (pintype "passive"))
      (node (ref "C30") (pin "2") (pinfunction "2_2") (pintype "passive"))
      (node (ref "C31") (pin "2") (pinfunction "2_2") (pintype "passive"))
      (node (ref "C32") (pin "2") (pinfunction "2_2") (pintype "passive"))
      (node (ref "C33") (pin "2") (pinfunction "2_2") (pintype "passive"))
      (node (ref "C34") (pin "2") (pinfunction "2_2") (pintype "passive"))
      (node (ref "C35") (pin "2") (pinfunction "2_2") (pintype "passive"))
      (node (ref "C4") (pin "2") (pinfunction "2_2") (pintype "passive"))
      (node (ref "C5") (pin "2") (pinfunction "2_2") (pintype "passive"))
      (node (ref "C6") (pin "2") (pinfunction "2_2") (pintype "passive"))
      (node (ref "C7") (pin "2") (pinfunction "2_2") (pintype "passive"))
      (node (ref "C8") (pin "2") (pinfunction "2_2") (pintype "passive"))
      (node (ref "C9") (pin "2") (pinfunction "2_2") (pintype "passive"))
      (node (ref "L4") (pin "1") (pinfunction "1_1") (pintype "passive"))
      (node (ref "R2") (pin "2") (pinfunction "2_2") (pintype "passive"))
      (node (ref "R3") (pin "2") (pinfunction "2_2") (pintype "passive"))
      (node (ref "R4") (pin "1") (pinfunction "1_1") (pintype "passive"))
      (node (ref "R7") (pin "1") (pinfunction "1_1") (pintype "passive"))
      (node (ref "Shield1") (pin "0") (pinfunction "Feed_0") (pintype "passive"))
      (node (ref "U1") (pin "A1") (pinfunction "GND_A1") (pintype "power_in"))
      (node (ref "U1") (pin "A11") (pinfunction "GND_A11") (pintype "power_in"))
      (node (ref "U1") (pin "B8") (pinfunction "GND_B8") (pintype "power_in"))
      (node (ref "U1") (pin "C15") (pinfunction "GND_C15") (pintype "power_in"))
      (node (ref "U1") (pin "C5") (pinfunction "GND_C5") (pintype "power_in"))
      (node (ref "U1") (pin "D12") (pinfunction "GND_D12") (pintype "power_in"))
      (node (ref "U1") (pin "D2") (pinfunction "GND_D2") (pintype "power_in"))
      (node (ref "U1") (pin "E5") (pinfunction "GND_E5") (pintype "power_in"))
      (node (ref "U1") (pin "E7") (pinfunction "GND_E7") (pintype "power_in"))
      (node (ref "U1") (pin "E8") (pinfunction "RSVDGND_E8") (pintype "power_in"))
      (node (ref "U1") (pin "E9") (pinfunction "GND_E9") (pintype "power_in"))
      (node (ref "U1") (pin "F10") (pinfunction "GND_F10") (pintype "power_in"))
      (node (ref "U1") (pin "G13") (pinfunction "GND_G13") (pintype "power_in"))
      (node (ref "U1") (pin "G3") (pinfunction "GND_G3") (pintype "power_in"))
      (node (ref "U1") (pin "G5") (pinfunction "GND_G5") (pintype "power_in"))
      (node (ref "U1") (pin "H10") (pinfunction "GND_H10") (pintype "power_in"))
      (node (ref "U1") (pin "H6") (pinfunction "GND_H6") (pintype "power_in"))
      (node (ref "U1") (pin "J5") (pinfunction "GND_J5") (pintype "power_in"))
      (node (ref "U1") (pin "J9") (pinfunction "GND_J9") (pintype "power_in"))
      (node (ref "U1") (pin "K10") (pinfunction "GND_K10") (pintype "power_in"))
      (node (ref "U1") (pin "K14") (pinfunction "GND_K14") (pintype "power_in"))
      (node (ref "U1") (pin "K4") (pinfunction "GND_K4") (pintype "power_in"))
      (node (ref "U1") (pin "K7") (pinfunction "GND_K7") (pintype "power_in"))
      (node (ref "U1") (pin "L1") (pinfunction "GND_L1") (pintype "power_in"))
      (node (ref "U1") (pin "L11") (pinfunction "GND_L11") (pintype "power_in"))
      (node (ref "U1") (pin "L5") (pinfunction "GND_L5") (pintype "power_in"))
      (node (ref "U1") (pin "M8") (pinfunction "GND_M8") (pintype "power_in"))
      (node (ref "U1") (pin "N15") (pinfunction "GND_N15") (pintype "power_in"))
      (node (ref "U1") (pin "N5") (pinfunction "GND_N5") (pintype "power_in"))
      (node (ref "U1") (pin "P12") (pinfunction "GND_P12") (pintype "power_in"))
      (node (ref "U1") (pin "P2") (pinfunction "GND_P2") (pintype "power_in"))
      (node (ref "U1") (pin "R9") (pinfunction "GND_R9") (pintype "power_in"))
      (node (ref "U2") (pin "1") (pinfunction "A0_1") (pintype "input"))
      (node (ref "U2") (pin "13") (pinfunction "A2_13") (pintype "input"))
      (node (ref "U2") (pin "17") (pinfunction "VSS_17") (pintype "passive"))
      (node (ref "U2") (pin "2") (pinfunction "A1_2") (pintype "input"))
      (node (ref "U2") (pin "8") (pinfunction "VSS_8") (pintype "passive"))
      (node (ref "Y1") (pin "2") (pinfunction "GND_2") (pintype "power_in"))
    )
    (net (code "190") (name "Net-(U1G-VCCPLL)") (class "Default")
      (node (ref "C1") (pin "2") (pinfunction "2_2") (pintype "passive"))
      (node (ref "C2") (pin "2") (pinfunction "2_2") (pintype "passive"))
      (node (ref "L1") (pin "1") (pinfunction "1_1") (pintype "passive"))
      (node (ref "U1") (pin "F5") (pinfunction "VCCPLL_F5") (pintype "power_in"))
    )
    (net (code "191") (name "Net-(U2-SC0)") (class "Default")
      (node (ref "TP71") (pin "1") (pintype "passive"))
      (node (ref "U2") (pin "5") (pinfunction "SC0_5") (pintype "input"))
    )
    (net (code "192") (name "Net-(U2-SD0)") (class "Default")
      (node (ref "TP72") (pin "1") (pintype "passive"))
      (node (ref "U2") (pin "4") (pinfunction "SD0_4") (pintype "input"))
    )
    (net (code "193") (name "Net-(Y1-OE{slash}!ST)") (class "Default")
      (node (ref "L2") (pin "1") (pinfunction "1_1") (pintype "passive"))
      (node (ref "Y1") (pin "1") (pinfunction "OE/!ST_1") (pintype "input"))
      (node (ref "Y1") (pin "4") (pinfunction "VDD_4") (pintype "power_in"))
    )
    (net (code "194") (name "Net-(Y1-OUT)") (class "Default")
      (node (ref "R8") (pin "1") (pinfunction "1_1") (pintype "passive"))
      (node (ref "Y1") (pin "3") (pinfunction "OUT_3") (pintype "output"))
    )
    (net (code "195") (name "VCC 1.0V") (class "Default")
      (node (ref "C29") (pin "1") (pinfunction "1_1") (pintype "passive"))
      (node (ref "C30") (pin "1") (pinfunction "1_1") (pintype "passive"))
      (node (ref "C31") (pin "1") (pinfunction "1_1") (pintype "passive"))
      (node (ref "C32") (pin "1") (pinfunction "1_1") (pintype "passive"))
      (node (ref "C33") (pin "1") (pinfunction "1_1") (pintype "passive"))
      (node (ref "C34") (pin "1") (pinfunction "1_1") (pintype "passive"))
      (node (ref "C35") (pin "1") (pinfunction "1_1") (pintype "passive"))
      (node (ref "U1") (pin "E10") (pinfunction "VCCINT_E10") (pintype "power_in"))
      (node (ref "U1") (pin "F9") (pinfunction "VCCINT_F9") (pintype "power_in"))
      (node (ref "U1") (pin "G10") (pinfunction "VCCINT_G10") (pintype "power_in"))
      (node (ref "U1") (pin "G6") (pinfunction "VCCPINT_G6") (pintype "power_in"))
      (node (ref "U1") (pin "H5") (pinfunction "VCCPINT_H5") (pintype "power_in"))
      (node (ref "U1") (pin "J10") (pinfunction "VCCINT_J10") (pintype "power_in"))
      (node (ref "U1") (pin "K5") (pinfunction "VCCPINT_K5") (pintype "power_in"))
      (node (ref "U1") (pin "L10") (pinfunction "VCCINT_L10") (pintype "power_in"))
    )
    (net (code "196") (name "VCC 1.8V") (class "Default")
      (node (ref "C10") (pin "1") (pinfunction "1_1") (pintype "passive"))
      (node (ref "C11") (pin "1") (pinfunction "1_1") (pintype "passive"))
      (node (ref "C12") (pin "1") (pinfunction "1_1") (pintype "passive"))
      (node (ref "C13") (pin "1") (pinfunction "1_1") (pintype "passive"))
      (node (ref "C14") (pin "1") (pinfunction "1_1") (pintype "passive"))
      (node (ref "C15") (pin "1") (pinfunction "1_1") (pintype "passive"))
      (node (ref "C23") (pin "1") (pinfunction "1_1") (pintype "passive"))
      (node (ref "C24") (pin "1") (pinfunction "1_1") (pintype "passive"))
      (node (ref "L1") (pin "2") (pinfunction "2_2") (pintype "passive"))
      (node (ref "L3") (pin "1") (pinfunction "1_1") (pintype "passive"))
      (node (ref "R9") (pin "2") (pinfunction "2_2") (pintype "passive"))
      (node (ref "U1") (pin "E6") (pinfunction "VCCBATT_0_E6") (pintype "power_in"))
      (node (ref "U1") (pin "F11") (pinfunction "VCCO_35_F11") (pintype "power_in"))
      (node (ref "U1") (pin "H15") (pinfunction "VCCO_35_H15") (pintype "power_in"))
      (node (ref "U1") (pin "H9") (pinfunction "VCCAUX_H9") (pintype "power_in"))
      (node (ref "U1") (pin "J6") (pinfunction "VCCPAUX_J6") (pintype "power_in"))
      (node (ref "U1") (pin "J8") (pinfunction "VCCAUX_J8") (pintype "power_in"))
      (node (ref "U1") (pin "K9") (pinfunction "VCCAUX_K9") (pintype "power_in"))
      (node (ref "U1") (pin "L6") (pinfunction "VCCPAUX_L6") (pintype "power_in"))
    )
    (net (code "197") (name "VCC 1.35V") (class "Default")
      (node (ref "C4") (pin "1") (pinfunction "1_1") (pintype "passive"))
      (node (ref "C5") (pin "1") (pinfunction "1_1") (pintype "passive"))
      (node (ref "C6") (pin "1") (pinfunction "1_1") (pintype "passive"))
      (node (ref "C7") (pin "1") (pinfunction "1_1") (pintype "passive"))
      (node (ref "C8") (pin "1") (pinfunction "1_1") (pintype "passive"))
      (node (ref "R5") (pin "1") (pinfunction "1_1") (pintype "passive"))
      (node (ref "R6") (pin "2") (pinfunction "2_2") (pintype "passive"))
      (node (ref "U1") (pin "B3") (pinfunction "VCCO_DDR_502_B3") (pintype "power_in"))
      (node (ref "U1") (pin "E4") (pinfunction "VCCO_DDR_502_E4") (pintype "power_in"))
      (node (ref "U1") (pin "F1") (pinfunction "VCCO_DDR_502_F1") (pintype "power_in"))
      (node (ref "U1") (pin "J2") (pinfunction "VCCO_DDR_502_J2") (pintype "power_in"))
      (node (ref "U1") (pin "M3") (pinfunction "VCCO_DDR_502_M3") (pintype "power_in"))
      (node (ref "U1") (pin "R4") (pinfunction "VCCO_DDR_502_R4") (pintype "power_in"))
    )
    (net (code "198") (name "VCC 3.3V") (class "Default")
      (node (ref "C16") (pin "2") (pinfunction "2_2") (pintype "passive"))
      (node (ref "C17") (pin "2") (pinfunction "2_2") (pintype "passive"))
      (node (ref "C18") (pin "1") (pinfunction "1_1") (pintype "passive"))
      (node (ref "C19") (pin "1") (pinfunction "1_1") (pintype "passive"))
      (node (ref "C21") (pin "2") (pinfunction "2_2") (pintype "passive"))
      (node (ref "C22") (pin "1") (pinfunction "1_1") (pintype "passive"))
      (node (ref "C25") (pin "1") (pinfunction "1_1") (pintype "passive"))
      (node (ref "C26") (pin "1") (pinfunction "1_1") (pintype "passive"))
      (node (ref "C27") (pin "1") (pinfunction "1_1") (pintype "passive"))
      (node (ref "C28") (pin "1") (pinfunction "1_1") (pintype "passive"))
      (node (ref "C9") (pin "1") (pinfunction "1_1") (pintype "passive"))
      (node (ref "L2") (pin "2") (pinfunction "2_2") (pintype "passive"))
      (node (ref "R1") (pin "2") (pinfunction "2_2") (pintype "passive"))
      (node (ref "R10") (pin "2") (pinfunction "2_2") (pintype "passive"))
      (node (ref "R11") (pin "2") (pinfunction "2_2") (pintype "passive"))
      (node (ref "U1") (pin "A6") (pinfunction "VCCO_MIO0_500_A6") (pintype "power_in"))
      (node (ref "U1") (pin "B11") (pinfunction "PS_SRST_B_501_B11") (pintype "input"))
      (node (ref "U1") (pin "B13") (pinfunction "VCCO_MIO1_501_B13") (pintype "power_in"))
      (node (ref "U1") (pin "C10") (pinfunction "VCCO_MIO1_501_C10") (pintype "power_in"))
      (node (ref "U1") (pin "D7") (pinfunction "VCCO_MIO0_500_D7") (pintype "power_in"))
      (node (ref "U1") (pin "E14") (pinfunction "VCCO_MIO1_501_E14") (pintype "power_in"))
      (node (ref "U1") (pin "F6") (pinfunction "CFGBVS_0_F6") (pintype "input"))
      (node (ref "U1") (pin "G4") (pinfunction "RSVDVCC1_G4") (pintype "power_in"))
      (node (ref "U1") (pin "H4") (pinfunction "RSVDVCC3_H4") (pintype "power_in"))
      (node (ref "U1") (pin "J12") (pinfunction "VCCO_34_J12") (pintype "power_in"))
      (node (ref "U1") (pin "J4") (pinfunction "RSVDVCC2_J4") (pintype "power_in"))
      (node (ref "U1") (pin "K8") (pinfunction "VCCO_0_K8") (pintype "power_in"))
      (node (ref "U1") (pin "M13") (pinfunction "VCCO_34_M13") (pintype "power_in"))
      (node (ref "U1") (pin "N10") (pinfunction "VCCO_34_N10") (pintype "power_in"))
      (node (ref "U1") (pin "P7") (pinfunction "VCCO_34_P7") (pintype "power_in"))
      (node (ref "U1") (pin "R14") (pinfunction "VCCO_34_R14") (pintype "power_in"))
      (node (ref "U2") (pin "16") (pinfunction "VDD_16") (pintype "power_in"))
    )
    (net (code "199") (name "VTTREF DDR3") (class "Default")
      (node (ref "C3") (pin "1") (pinfunction "1_1") (pintype "passive"))
      (node (ref "R6") (pin "1") (pinfunction "1_1") (pintype "passive"))
      (node (ref "R7") (pin "2") (pinfunction "2_2") (pintype "passive"))
      (node (ref "TP1") (pin "1") (pintype "passive"))
      (node (ref "U1") (pin "F4") (pinfunction "PS_DDR_VREF0_502_F4") (pintype "input"))
    )
    (net (code "200") (name "unconnected-(U1C-DXP_0-PadJ7)") (class "Default")
      (node (ref "U1") (pin "J7") (pinfunction "DXP_0_J7") (pintype "input+no_connect"))
    )
  )
)
